# mcu.net
KiCad netlist of a schematic drawn in Altium Designer
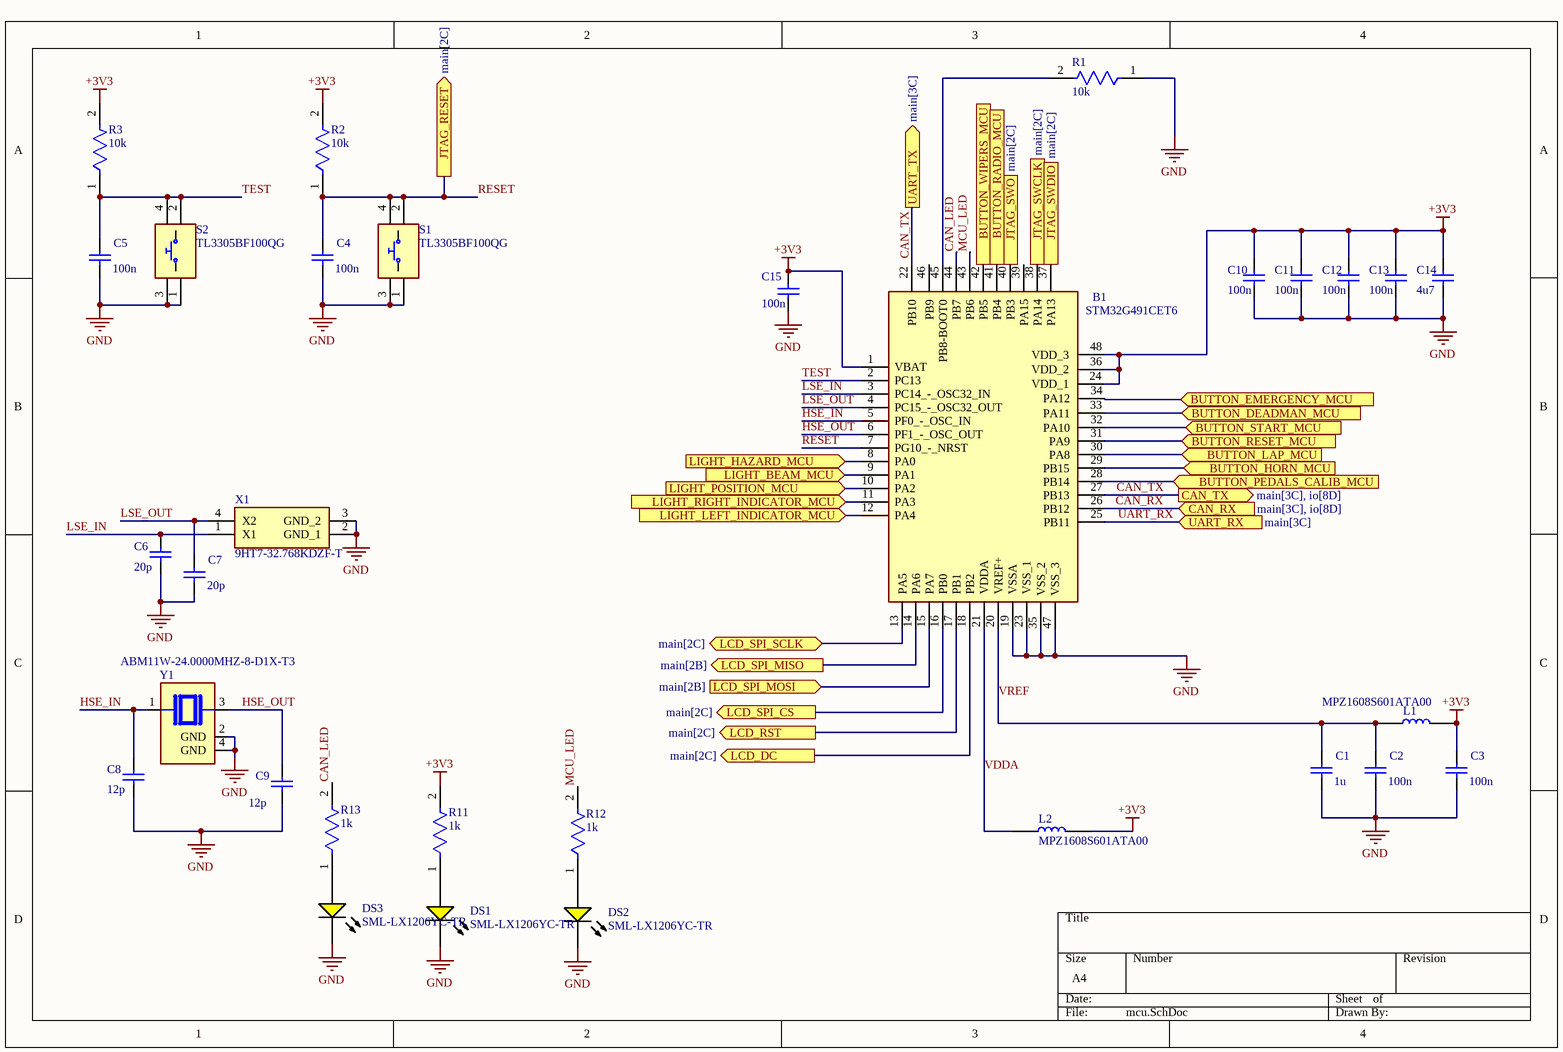
[diagram p0: mcu.SchDoc]

(export (version "E")
  (design (tool "Eeschema 10.0.6"))
  (components
    (comp (ref "B1")
      (value "STM32G491CET6")
      (footprint "STM32G491CET6")
      (description "ARM Microcontrollers - MCU Mainstream Arm Cortex-M4+ MCU 170MHz with 512Kbytes of Flash memory")
      (fields (field (name "MOUSER PART NUMBER") "511-STM32G491CET6"))
      (libsource (lib "HydrogreenLibrary") (part "STM32G491CET6"))
    )
    (comp (ref "C1")
      (value "1u")
      (footprint "CAPC1206(3216)150_L")
      (description "CAP 1.8uF 10V ±5% 1206 (3216 Metric) Thickness 1.45mm SMD")
      (fields (field (name "TOLERANCE") "Â±5%"))
      (libsource (lib "Altium Content Vault") (part "CAP"))
    )
    (comp (ref "C2")
      (value "100n")
      (footprint "CAPC1206(3216)150_L")
      (description "CAP 1.8uF 10V ±5% 1206 (3216 Metric) Thickness 1.45mm SMD")
      (fields (field (name "TOLERANCE") "Â±5%"))
      (libsource (lib "Altium Content Vault") (part "CAP"))
    )
    (comp (ref "C3")
      (value "100n")
      (footprint "CAPC1206(3216)150_L")
      (description "CAP 1.8uF 10V ±5% 1206 (3216 Metric) Thickness 1.45mm SMD")
      (fields (field (name "TOLERANCE") "Â±5%"))
      (libsource (lib "Altium Content Vault") (part "CAP"))
    )
    (comp (ref "C4")
      (value "100n")
      (footprint "CAPC1206(3216)150_L")
      (description "CAP 1.8uF 10V ±5% 1206 (3216 Metric) Thickness 1.45mm SMD")
      (fields (field (name "TOLERANCE") "Â±5%"))
      (libsource (lib "Altium Content Vault") (part "CAP"))
    )
    (comp (ref "C5")
      (value "100n")
      (footprint "CAPC1206(3216)150_L")
      (description "CAP 1.8uF 10V ±5% 1206 (3216 Metric) Thickness 1.45mm SMD")
      (fields (field (name "TOLERANCE") "Â±5%"))
      (libsource (lib "Altium Content Vault") (part "CAP"))
    )
    (comp (ref "C6")
      (value "20p")
      (footprint "CAPC1206(3216)150_L")
      (description "CAP 1.8uF 10V ±5% 1206 (3216 Metric) Thickness 1.45mm SMD")
      (fields (field (name "TOLERANCE") "Â±5%"))
      (libsource (lib "Altium Content Vault") (part "CAP"))
    )
    (comp (ref "C7")
      (value "20p")
      (footprint "CAPC1206(3216)150_L")
      (description "CAP 1.8uF 10V ±5% 1206 (3216 Metric) Thickness 1.45mm SMD")
      (fields (field (name "TOLERANCE") "Â±5%"))
      (libsource (lib "Altium Content Vault") (part "CAP"))
    )
    (comp (ref "C8")
      (value "12p")
      (footprint "CAPC1206(3216)150_L")
      (description "CAP 1.8uF 10V ±5% 1206 (3216 Metric) Thickness 1.45mm SMD")
      (fields (field (name "TOLERANCE") "Â±5%"))
      (libsource (lib "Altium Content Vault") (part "CAP"))
    )
    (comp (ref "C9")
      (value "12p")
      (footprint "CAPC1206(3216)150_L")
      (description "CAP 1.8uF 10V ±5% 1206 (3216 Metric) Thickness 1.45mm SMD")
      (fields (field (name "TOLERANCE") "Â±5%"))
      (libsource (lib "Altium Content Vault") (part "CAP"))
    )
    (comp (ref "C10")
      (value "100n")
      (footprint "CAPC1206(3216)150_L")
      (description "CAP 1.8uF 10V ±5% 1206 (3216 Metric) Thickness 1.45mm SMD")
      (fields (field (name "TOLERANCE") "Â±5%"))
      (libsource (lib "Altium Content Vault") (part "CAP"))
    )
    (comp (ref "C11")
      (value "100n")
      (footprint "CAPC1206(3216)150_L")
      (description "CAP 1.8uF 10V ±5% 1206 (3216 Metric) Thickness 1.45mm SMD")
      (fields (field (name "TOLERANCE") "Â±5%"))
      (libsource (lib "Altium Content Vault") (part "CAP"))
    )
    (comp (ref "C12")
      (value "100n")
      (footprint "CAPC1206(3216)150_L")
      (description "CAP 1.8uF 10V ±5% 1206 (3216 Metric) Thickness 1.45mm SMD")
      (fields (field (name "TOLERANCE") "Â±5%"))
      (libsource (lib "Altium Content Vault") (part "CAP"))
    )
    (comp (ref "C13")
      (value "100n")
      (footprint "CAPC1206(3216)150_L")
      (description "CAP 1.8uF 10V ±5% 1206 (3216 Metric) Thickness 1.45mm SMD")
      (fields (field (name "TOLERANCE") "Â±5%"))
      (libsource (lib "Altium Content Vault") (part "CAP"))
    )
    (comp (ref "C14")
      (value "4u7")
      (footprint "CAPC1206(3216)150_L")
      (description "CAP 1.8uF 10V ±5% 1206 (3216 Metric) Thickness 1.45mm SMD")
      (fields (field (name "TOLERANCE") "Â±5%"))
      (libsource (lib "Altium Content Vault") (part "CAP"))
    )
    (comp (ref "C15")
      (value "100n")
      (footprint "CAPC1206(3216)150_L")
      (description "CAP 1.8uF 10V ±5% 1206 (3216 Metric) Thickness 1.45mm SMD")
      (fields (field (name "TOLERANCE") "Â±5%"))
      (libsource (lib "Altium Content Vault") (part "CAP"))
    )
    (comp (ref "DS1")
      (value "SML-LX1206YC-TR")
      (footprint "LUMX-SML-LX1206YC-TR_V")
      (description "Yellow LED, Water Clear Len, 585 nm, 2.1 V, -40 to 85 degC, 2-Pin SMD, RoHS, Tape and Reel")
      (fields (field (name "MANUFACTURER") "Lumex"))
      (libsource (lib "Altium Content Vault") (part "LED-YELLOW-AK-2"))
    )
    (comp (ref "DS2")
      (value "SML-LX1206YC-TR")
      (footprint "LUMX-SML-LX1206YC-TR_V")
      (description "Yellow LED, Water Clear Len, 585 nm, 2.1 V, -40 to 85 degC, 2-Pin SMD, RoHS, Tape and Reel")
      (fields (field (name "MANUFACTURER") "Lumex"))
      (libsource (lib "Altium Content Vault") (part "LED-YELLOW-AK-2"))
    )
    (comp (ref "DS3")
      (value "SML-LX1206YC-TR")
      (footprint "LUMX-SML-LX1206YC-TR_V")
      (description "Yellow LED, Water Clear Len, 585 nm, 2.1 V, -40 to 85 degC, 2-Pin SMD, RoHS, Tape and Reel")
      (fields (field (name "MANUFACTURER") "Lumex"))
      (libsource (lib "Altium Content Vault") (part "LED-YELLOW-AK-2"))
    )
    (comp (ref "L1")
      (value "MPZ1608S601ATA00")
      (footprint "INDC1608X95N")
      (description "Ferrite Beads Multi-Layer 600Ohm 25% 100MHz 1A 0.15Ohm DCR 0603 T/R")
      (fields (field (name "MF") "TDK") (field (name "TOLERANCE") "25%"))
      (libsource (lib "HydrogreenLibrary") (part "MPZ1608S601ATA00"))
    )
    (comp (ref "L2")
      (value "MPZ1608S601ATA00")
      (footprint "INDC1608X95N")
      (description "Ferrite Beads Multi-Layer 600Ohm 25% 100MHz 1A 0.15Ohm DCR 0603 T/R")
      (fields (field (name "MF") "TDK") (field (name "TOLERANCE") "25%"))
      (libsource (lib "HydrogreenLibrary") (part "MPZ1608S601ATA00"))
    )
    (comp (ref "R1")
      (value "10k")
      (footprint "FP-RK73H2B-MFG")
      (description "40.2kΩ ±1% 0.25W Chip Resistor 1206 Thick Film AEC-Q200 Qualified")
      (fields (field (name "TOLERANCE") "1%"))
      (libsource (lib "Altium Content Vault") (part "1029c3af85768c4190bb7ad29bc67b5"))
    )
    (comp (ref "R2")
      (value "10k")
      (footprint "FP-RK73H2B-MFG")
      (description "40.2kΩ ±1% 0.25W Chip Resistor 1206 Thick Film AEC-Q200 Qualified")
      (fields (field (name "TOLERANCE") "1%"))
      (libsource (lib "Altium Content Vault") (part "1029c3af85768c4190bb7ad29bc67b5"))
    )
    (comp (ref "R3")
      (value "10k")
      (footprint "FP-RK73H2B-MFG")
      (description "40.2kΩ ±1% 0.25W Chip Resistor 1206 Thick Film AEC-Q200 Qualified")
      (fields (field (name "TOLERANCE") "1%"))
      (libsource (lib "Altium Content Vault") (part "1029c3af85768c4190bb7ad29bc67b5"))
    )
    (comp (ref "R11")
      (value "1k")
      (footprint "FP-RK73H2B-MFG")
      (description "40.2kΩ ±1% 0.25W Chip Resistor 1206 Thick Film AEC-Q200 Qualified")
      (fields (field (name "TOLERANCE") "1%"))
      (libsource (lib "Altium Content Vault") (part "1029c3af85768c4190bb7ad29bc67b5"))
    )
    (comp (ref "R12")
      (value "1k")
      (footprint "FP-RK73H2B-MFG")
      (description "40.2kΩ ±1% 0.25W Chip Resistor 1206 Thick Film AEC-Q200 Qualified")
      (fields (field (name "TOLERANCE") "1%"))
      (libsource (lib "Altium Content Vault") (part "1029c3af85768c4190bb7ad29bc67b5"))
    )
    (comp (ref "R13")
      (value "1k")
      (footprint "FP-RK73H2B-MFG")
      (description "40.2kΩ ±1% 0.25W Chip Resistor 1206 Thick Film AEC-Q200 Qualified")
      (fields (field (name "TOLERANCE") "1%"))
      (libsource (lib "Altium Content Vault") (part "1029c3af85768c4190bb7ad29bc67b5"))
    )
    (comp (ref "S1")
      (value "TL3305BF100QG")
      (footprint "TL3305BF160QG")
      (description "TL3305 Ultra-Miniature Tact Switch 100gf 5.0mm actuator Silver Contact Gullwing")
      (fields
        (field (name "MOUSER PART NUMBER") "612-TL3305BF100QG")
        (field (name "MANUFACTURER") "E-Switch")
      )
      (libsource (lib "HydrogreenLibrary") (part "TL3305BF100QG"))
    )
    (comp (ref "S2")
      (value "TL3305BF100QG")
      (footprint "TL3305BF160QG")
      (description "TL3305 Ultra-Miniature Tact Switch 100gf 5.0mm actuator Silver Contact Gullwing")
      (fields
        (field (name "MOUSER PART NUMBER") "612-TL3305BF100QG")
        (field (name "MANUFACTURER") "E-Switch")
      )
      (libsource (lib "HydrogreenLibrary") (part "TL3305BF100QG"))
    )
    (comp (ref "X1")
      (value "9HT7-32.768KDZF-T")
      (footprint "9HT732768KDZFT")
      (description "Parallel - Fundamental Quartz Crystal, 0.032768MHz Nom")
      (fields (field (name "MOUSER PART NUMBER") "717-9HT7-32.768KDZFT") (field (name "MANUFACTURER") "TXC"))
      (libsource (lib "HydrogreenLibrary") (part "9HT7-32.768KDZF-T"))
    )
    (comp (ref "Y1")
      (value "ABM11W-24.0000MHZ-8-D1X-T3")
      (footprint "XTAL_ABM11W-24.0000MHZ-8-D1X-T3")
      (description "Crystal, Quartz, 24 MHz, SMD, 2mm x 1.6mm x 0.5mm, 20 ppm, 8 pF, 10 ppm, ABM11W")
      (fields (field (name "MF") "Abracon LLC") (field (name "MANUFACTURER") "Abracon"))
      (libsource (lib "HydrogreenLibrary") (part "ABM11W-24.0000MHZ-8-D1X-T3"))
    )
  )
  (nets
    (net (code "1") (name "+3V3") (class "Default")
      (node (ref "B1") (pin "1") (pinfunction "VBAT_1") (pintype "passive"))
      (node (ref "B1") (pin "24") (pinfunction "VDD_1_24") (pintype "passive"))
      (node (ref "B1") (pin "36") (pinfunction "VDD_2_36") (pintype "passive"))
      (node (ref "B1") (pin "48") (pinfunction "VDD_3_48") (pintype "passive"))
      (node (ref "C10") (pin "1") (pinfunction "1_1") (pintype "passive"))
      (node (ref "C11") (pin "1") (pinfunction "1_1") (pintype "passive"))
      (node (ref "C12") (pin "1") (pinfunction "1_1") (pintype "passive"))
      (node (ref "C13") (pin "1") (pinfunction "1_1") (pintype "passive"))
      (node (ref "C14") (pin "1") (pinfunction "1_1") (pintype "passive"))
      (node (ref "C15") (pin "1") (pinfunction "1_1") (pintype "passive"))
      (node (ref "C3") (pin "1") (pinfunction "1_1") (pintype "passive"))
      (node (ref "L1") (pin "2") (pinfunction "2_2") (pintype "passive"))
      (node (ref "L2") (pin "2") (pinfunction "2_2") (pintype "passive"))
      (node (ref "R11") (pin "2") (pinfunction "2_2") (pintype "passive"))
      (node (ref "R2") (pin "2") (pinfunction "2_2") (pintype "passive"))
      (node (ref "R3") (pin "2") (pinfunction "2_2") (pintype "passive"))
    )
    (net (code "2") (name "/BUTTON_DEADMAN_MCU") (class "Default")
      (node (ref "B1") (pin "33") (pinfunction "PA11_33") (pintype "passive"))
    )
    (net (code "3") (name "/BUTTON_EMERGENCY_MCU") (class "Default")
      (node (ref "B1") (pin "34") (pinfunction "PA12_34") (pintype "passive"))
    )
    (net (code "4") (name "/BUTTON_HORN_MCU") (class "Default")
      (node (ref "B1") (pin "29") (pinfunction "PB15_29") (pintype "passive"))
    )
    (net (code "5") (name "/BUTTON_LAP_MCU") (class "Default")
      (node (ref "B1") (pin "30") (pinfunction "PA8_30") (pintype "passive"))
    )
    (net (code "6") (name "/BUTTON_PEDALS_CALIB_MCU") (class "Default")
      (node (ref "B1") (pin "28") (pinfunction "PB14_28") (pintype "passive"))
    )
    (net (code "7") (name "/BUTTON_RADIO_MCU") (class "Default")
      (node (ref "B1") (pin "41") (pinfunction "PB4_41") (pintype "passive"))
    )
    (net (code "8") (name "/BUTTON_RESET_MCU") (class "Default")
      (node (ref "B1") (pin "31") (pinfunction "PA9_31") (pintype "passive"))
    )
    (net (code "9") (name "/BUTTON_START_MCU") (class "Default")
      (node (ref "B1") (pin "32") (pinfunction "PA10_32") (pintype "passive"))
    )
    (net (code "10") (name "/BUTTON_WIPERS_MCU") (class "Default")
      (node (ref "B1") (pin "42") (pinfunction "PB5_42") (pintype "passive"))
    )
    (net (code "11") (name "/CAN_LED") (class "Default")
      (node (ref "B1") (pin "44") (pinfunction "PB7_44") (pintype "passive"))
      (node (ref "R13") (pin "2") (pinfunction "2_2") (pintype "passive"))
    )
    (net (code "12") (name "/CAN_RX") (class "Default")
      (node (ref "B1") (pin "26") (pinfunction "PB12_26") (pintype "passive"))
    )
    (net (code "13") (name "/CAN_TX") (class "Default")
      (node (ref "B1") (pin "27") (pinfunction "PB13_27") (pintype "passive"))
    )
    (net (code "14") (name "/HSE_IN") (class "Default")
      (node (ref "B1") (pin "5") (pinfunction "PF0_-_OSC_IN_5") (pintype "passive"))
      (node (ref "C8") (pin "1") (pinfunction "1_1") (pintype "passive"))
      (node (ref "Y1") (pin "1") (pinfunction "1_1") (pintype "passive"))
    )
    (net (code "15") (name "/HSE_OUT") (class "Default")
      (node (ref "B1") (pin "6") (pinfunction "PF1_-_OSC_OUT_6") (pintype "passive"))
      (node (ref "C9") (pin "1") (pinfunction "1_1") (pintype "passive"))
      (node (ref "Y1") (pin "3") (pinfunction "2_3") (pintype "passive"))
    )
    (net (code "16") (name "/JTAG_SWCLK") (class "Default")
      (node (ref "B1") (pin "38") (pinfunction "PA14_38") (pintype "passive"))
    )
    (net (code "17") (name "/JTAG_SWDIO") (class "Default")
      (node (ref "B1") (pin "37") (pinfunction "PA13_37") (pintype "passive"))
    )
    (net (code "18") (name "/JTAG_SWO") (class "Default")
      (node (ref "B1") (pin "40") (pinfunction "PB3_40") (pintype "passive"))
    )
    (net (code "19") (name "/LCD_DC") (class "Default")
      (node (ref "B1") (pin "18") (pinfunction "PB2_18") (pintype "passive"))
    )
    (net (code "20") (name "/LCD_RST") (class "Default")
      (node (ref "B1") (pin "17") (pinfunction "PB1_17") (pintype "passive"))
    )
    (net (code "21") (name "/LCD_SPI_CS") (class "Default")
      (node (ref "B1") (pin "16") (pinfunction "PB0_16") (pintype "passive"))
    )
    (net (code "22") (name "/LCD_SPI_MISO") (class "Default")
      (node (ref "B1") (pin "14") (pinfunction "PA6_14") (pintype "passive"))
    )
    (net (code "23") (name "/LCD_SPI_MOSI") (class "Default")
      (node (ref "B1") (pin "15") (pinfunction "PA7_15") (pintype "passive"))
    )
    (net (code "24") (name "/LCD_SPI_SCLK") (class "Default")
      (node (ref "B1") (pin "13") (pinfunction "PA5_13") (pintype "passive"))
    )
    (net (code "25") (name "/LIGHT_BEAM_MCU") (class "Default")
      (node (ref "B1") (pin "9") (pinfunction "PA1_9") (pintype "passive"))
    )
    (net (code "26") (name "/LIGHT_HAZARD_MCU") (class "Default")
      (node (ref "B1") (pin "8") (pinfunction "PA0_8") (pintype "passive"))
    )
    (net (code "27") (name "/LIGHT_LEFT_INDICATOR_MCU") (class "Default")
      (node (ref "B1") (pin "12") (pinfunction "PA4_12") (pintype "passive"))
    )
    (net (code "28") (name "/LIGHT_POSITION_MCU") (class "Default")
      (node (ref "B1") (pin "10") (pinfunction "PA2_10") (pintype "passive"))
    )
    (net (code "29") (name "/LIGHT_RIGHT_INDICATOR_MCU") (class "Default")
      (node (ref "B1") (pin "11") (pinfunction "PA3_11") (pintype "passive"))
    )
    (net (code "30") (name "/LSE_IN") (class "Default")
      (node (ref "B1") (pin "3") (pinfunction "PC14_-_OSC32_IN_3") (pintype "passive"))
      (node (ref "C6") (pin "1") (pinfunction "1_1") (pintype "passive"))
      (node (ref "X1") (pin "1") (pinfunction "X1_1") (pintype "passive"))
    )
    (net (code "31") (name "/LSE_OUT") (class "Default")
      (node (ref "B1") (pin "4") (pinfunction "PC15_-_OSC32_OUT_4") (pintype "passive"))
      (node (ref "C7") (pin "1") (pinfunction "1_1") (pintype "passive"))
      (node (ref "X1") (pin "4") (pinfunction "X2_4") (pintype "passive"))
    )
    (net (code "32") (name "/MCU_LED") (class "Default")
      (node (ref "B1") (pin "43") (pinfunction "PB6_43") (pintype "passive"))
      (node (ref "R12") (pin "2") (pinfunction "2_2") (pintype "passive"))
    )
    (net (code "33") (name "/RESET") (class "Default")
      (node (ref "B1") (pin "7") (pinfunction "PG10_-_NRST_7") (pintype "passive"))
      (node (ref "C4") (pin "1") (pinfunction "1_1") (pintype "passive"))
      (node (ref "R2") (pin "1") (pinfunction "1_1") (pintype "passive"))
      (node (ref "S1") (pin "2") (pintype "passive"))
      (node (ref "S1") (pin "4") (pintype "passive"))
    )
    (net (code "34") (name "/TEST") (class "Default")
      (node (ref "B1") (pin "2") (pinfunction "PC13_2") (pintype "passive"))
      (node (ref "C5") (pin "1") (pinfunction "1_1") (pintype "passive"))
      (node (ref "R3") (pin "1") (pinfunction "1_1") (pintype "passive"))
      (node (ref "S2") (pin "2") (pintype "passive"))
      (node (ref "S2") (pin "4") (pintype "passive"))
    )
    (net (code "35") (name "/UART_RX") (class "Default")
      (node (ref "B1") (pin "25") (pinfunction "PB11_25") (pintype "passive"))
    )
    (net (code "36") (name "/UART_TX") (class "Default")
      (node (ref "B1") (pin "22") (pinfunction "PB10_22") (pintype "passive"))
    )
    (net (code "37") (name "/VDDA") (class "Default")
      (node (ref "B1") (pin "21") (pinfunction "VDDA_21") (pintype "passive"))
      (node (ref "L2") (pin "1") (pinfunction "1_1") (pintype "passive"))
    )
    (net (code "38") (name "/VREF") (class "Default")
      (node (ref "B1") (pin "20") (pinfunction "VREF+_20") (pintype "passive"))
      (node (ref "C1") (pin "1") (pinfunction "1_1") (pintype "passive"))
      (node (ref "C2") (pin "1") (pinfunction "1_1") (pintype "passive"))
      (node (ref "L1") (pin "1") (pinfunction "1_1") (pintype "passive"))
    )
    (net (code "39") (name "GND") (class "Default")
      (node (ref "B1") (pin "19") (pinfunction "VSSA_19") (pintype "passive"))
      (node (ref "B1") (pin "23") (pinfunction "VSS_1_23") (pintype "passive"))
      (node (ref "B1") (pin "35") (pinfunction "VSS_2_35") (pintype "passive"))
      (node (ref "B1") (pin "47") (pinfunction "VSS_3_47") (pintype "passive"))
      (node (ref "C1") (pin "2") (pinfunction "2_2") (pintype "passive"))
      (node (ref "C10") (pin "2") (pinfunction "2_2") (pintype "passive"))
      (node (ref "C11") (pin "2") (pinfunction "2_2") (pintype "passive"))
      (node (ref "C12") (pin "2") (pinfunction "2_2") (pintype "passive"))
      (node (ref "C13") (pin "2") (pinfunction "2_2") (pintype "passive"))
      (node (ref "C14") (pin "2") (pinfunction "2_2") (pintype "passive"))
      (node (ref "C15") (pin "2") (pinfunction "2_2") (pintype "passive"))
      (node (ref "C2") (pin "2") (pinfunction "2_2") (pintype "passive"))
      (node (ref "C3") (pin "2") (pinfunction "2_2") (pintype "passive"))
      (node (ref "C4") (pin "2") (pinfunction "2_2") (pintype "passive"))
      (node (ref "C5") (pin "2") (pinfunction "2_2") (pintype "passive"))
      (node (ref "C6") (pin "2") (pinfunction "2_2") (pintype "passive"))
      (node (ref "C7") (pin "2") (pinfunction "2_2") (pintype "passive"))
      (node (ref "C8") (pin "2") (pinfunction "2_2") (pintype "passive"))
      (node (ref "C9") (pin "2") (pinfunction "2_2") (pintype "passive"))
      (node (ref "DS1") (pin "2") (pinfunction "K_2") (pintype "passive"))
      (node (ref "DS2") (pin "2") (pinfunction "K_2") (pintype "passive"))
      (node (ref "DS3") (pin "2") (pinfunction "K_2") (pintype "passive"))
      (node (ref "R1") (pin "1") (pinfunction "1_1") (pintype "passive"))
      (node (ref "S1") (pin "1") (pintype "passive"))
      (node (ref "S1") (pin "3") (pintype "passive"))
      (node (ref "S2") (pin "1") (pintype "passive"))
      (node (ref "S2") (pin "3") (pintype "passive"))
      (node (ref "X1") (pin "2") (pinfunction "GND_1_2") (pintype "passive"))
      (node (ref "X1") (pin "3") (pinfunction "GND_2_3") (pintype "passive"))
      (node (ref "Y1") (pin "2") (pinfunction "GND_2") (pintype "power_in"))
      (node (ref "Y1") (pin "4") (pinfunction "GND_4") (pintype "power_in"))
    )
    (net (code "40") (name "Net-(B1-PB8-BOOT0)") (class "Default")
      (node (ref "B1") (pin "45") (pinfunction "PB8-BOOT0_45") (pintype "passive"))
      (node (ref "R1") (pin "2") (pinfunction "2_2") (pintype "passive"))
    )
    (net (code "41") (name "Net-(DS1-A)") (class "Default")
      (node (ref "DS1") (pin "1") (pinfunction "A_1") (pintype "passive"))
      (node (ref "R11") (pin "1") (pinfunction "1_1") (pintype "passive"))
    )
    (net (code "42") (name "Net-(DS2-A)") (class "Default")
      (node (ref "DS2") (pin "1") (pinfunction "A_1") (pintype "passive"))
      (node (ref "R12") (pin "1") (pinfunction "1_1") (pintype "passive"))
    )
    (net (code "43") (name "Net-(DS3-A)") (class "Default")
      (node (ref "DS3") (pin "1") (pinfunction "A_1") (pintype "passive"))
      (node (ref "R13") (pin "1") (pinfunction "1_1") (pintype "passive"))
    )
    (net (code "44") (name "unconnected-(B1-PA15-Pad39)") (class "Default")
      (node (ref "B1") (pin "39") (pinfunction "PA15_39") (pintype "passive"))
    )
    (net (code "45") (name "unconnected-(B1-PB9-Pad46)") (class "Default")
      (node (ref "B1") (pin "46") (pinfunction "PB9_46") (pintype "passive"))
    )
  )
)
